# shutter_control.net
KiCad netlist of a schematic drawn in EAGLE
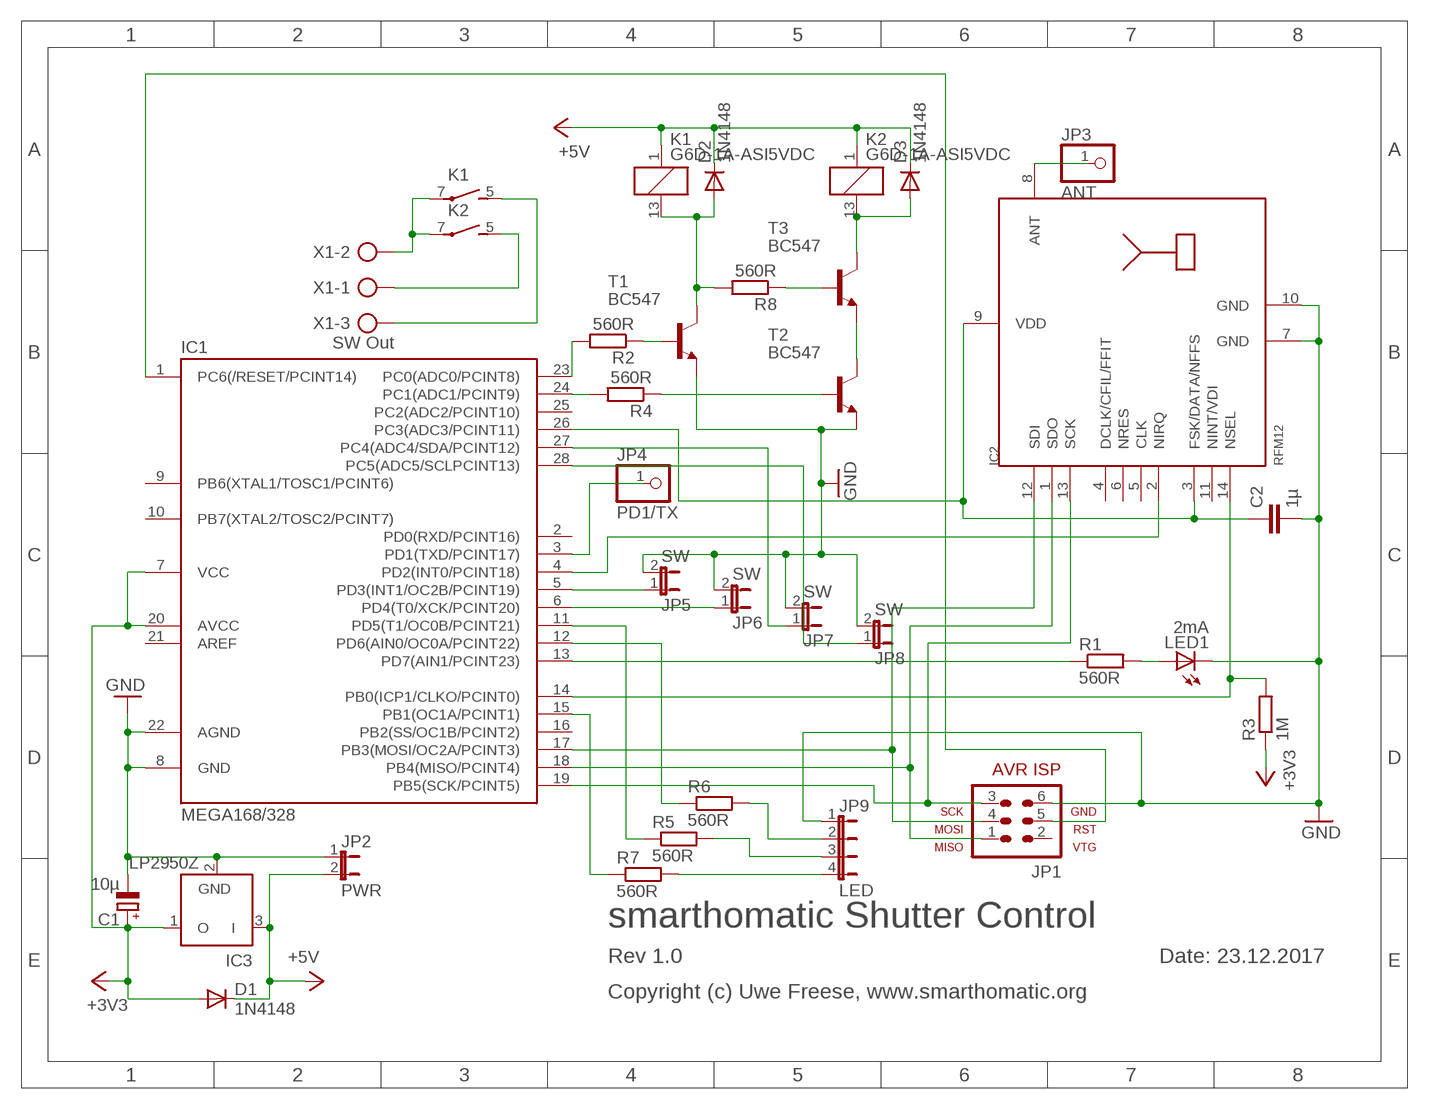
[diagram p0: schematic, sheet 1]

(export (version "E")
  (design (tool "Eeschema 10.0.6"))
  (components
    (comp (ref "C1")
      (value "10µ")
      (footprint "eagle-import:E1,8-4")
      (libsource (lib "eagle-import") (part "CPOL-EUE1.8-4"))
    )
    (comp (ref "C2")
      (value "1µ")
      (footprint "eagle-import:C5B3.5")
      (libsource (lib "eagle-import") (part "C5/3.5"))
    )
    (comp (ref "D1")
      (value "1N4148")
      (footprint "eagle-import:DO35-7")
      (libsource (lib "eagle-import") (part "1N4148DO35-7"))
    )
    (comp (ref "D2")
      (value "1N4148")
      (footprint "eagle-import:DO35-7")
      (libsource (lib "eagle-import") (part "1N4148DO35-7"))
    )
    (comp (ref "D3")
      (value "1N4148")
      (footprint "eagle-import:DO35-7")
      (libsource (lib "eagle-import") (part "1N4148DO35-7"))
    )
    (comp (ref "IC1")
      (value "MEGA168/328")
      (footprint "eagle-import:DIL28-3")
      (libsource (lib "eagle-import") (part "MEGA48/88/168-PU"))
    )
    (comp (ref "IC2")
      (value "RFM12")
      (footprint "eagle-import:RFM")
      (libsource (lib "eagle-import") (part "RFM12"))
    )
    (comp (ref "IC3")
      (value "LP2950Z")
      (footprint "eagle-import:TO92")
      (libsource (lib "eagle-import") (part "LP2950Z"))
    )
    (comp (ref "JP1")
      (value "AVR-ISP-6")
      (footprint "eagle-import:AVR-ISP-6")
      (libsource (lib "eagle-import") (part "AVR-ISP-6"))
    )
    (comp (ref "JP2")
      (value "PWR")
      (footprint "eagle-import:JP1")
      (libsource (lib "eagle-import") (part "JP1E"))
    )
    (comp (ref "JP3")
      (value "ANT")
      (footprint "eagle-import:1X01")
      (libsource (lib "eagle-import") (part "PINHD-1X1"))
    )
    (comp (ref "JP4")
      (value "PD1/TX")
      (footprint "eagle-import:1X01")
      (libsource (lib "eagle-import") (part "PINHD-1X1"))
    )
    (comp (ref "JP5")
      (value "SW")
      (footprint "eagle-import:JP1")
      (libsource (lib "eagle-import") (part "JP1E"))
    )
    (comp (ref "JP6")
      (value "SW")
      (footprint "eagle-import:JP1")
      (libsource (lib "eagle-import") (part "JP1E"))
    )
    (comp (ref "JP7")
      (value "SW")
      (footprint "eagle-import:JP1")
      (libsource (lib "eagle-import") (part "JP1E"))
    )
    (comp (ref "JP8")
      (value "SW")
      (footprint "eagle-import:JP1")
      (libsource (lib "eagle-import") (part "JP1E"))
    )
    (comp (ref "JP9")
      (value "LED")
      (footprint "eagle-import:JP4")
      (libsource (lib "eagle-import") (part "JP4E"))
    )
    (comp (ref "K1")
      (value "G6D-1A-ASI5VDC")
      (footprint "eagle-import:G6D")
      (libsource (lib "eagle-import") (part "G6D?-1A-ASI5VDC"))
    )
    (comp (ref "K2")
      (value "G6D-1A-ASI5VDC")
      (footprint "eagle-import:G6D")
      (libsource (lib "eagle-import") (part "G6D?-1A-ASI5VDC"))
    )
    (comp (ref "LED1")
      (value "2mA")
      (footprint "eagle-import:LED3MM")
      (libsource (lib "eagle-import") (part "LED3MM"))
    )
    (comp (ref "R1")
      (value "560R")
      (footprint "eagle-import:0207_7")
      (libsource (lib "eagle-import") (part "R-EU_0207/7"))
    )
    (comp (ref "R2")
      (value "560R")
      (footprint "eagle-import:0207_7")
      (libsource (lib "eagle-import") (part "R-EU_0207/7"))
    )
    (comp (ref "R3")
      (value "1M")
      (footprint "eagle-import:0207_7")
      (libsource (lib "eagle-import") (part "R-EU_0207/7"))
    )
    (comp (ref "R4")
      (value "560R")
      (footprint "eagle-import:0207_7")
      (libsource (lib "eagle-import") (part "R-EU_0207/7"))
    )
    (comp (ref "R5")
      (value "560R")
      (footprint "eagle-import:0207_7")
      (libsource (lib "eagle-import") (part "R-EU_0207/7"))
    )
    (comp (ref "R6")
      (value "560R")
      (footprint "eagle-import:0207_7")
      (libsource (lib "eagle-import") (part "R-EU_0207/7"))
    )
    (comp (ref "R7")
      (value "560R")
      (footprint "eagle-import:0207_7")
      (libsource (lib "eagle-import") (part "R-EU_0207/7"))
    )
    (comp (ref "R8")
      (value "560R")
      (footprint "eagle-import:0207_7")
      (libsource (lib "eagle-import") (part "R-EU_0207/7"))
    )
    (comp (ref "T1")
      (value "BC547")
      (footprint "eagle-import:TO92")
      (libsource (lib "eagle-import") (part "BC547"))
    )
    (comp (ref "T2")
      (value "BC547")
      (footprint "eagle-import:TO92")
      (libsource (lib "eagle-import") (part "BC547"))
    )
    (comp (ref "T3")
      (value "BC547")
      (footprint "eagle-import:TO92")
      (libsource (lib "eagle-import") (part "BC547"))
    )
    (comp (ref "X1")
      (value "SW Out")
      (footprint "eagle-import:AK500_3")
      (libsource (lib "eagle-import") (part "AK500/3"))
    )
  )
  (nets
    (net (code "1") (name "+3V3") (class "Default")
      (node (ref "C1") (pin "+") (pinfunction "+_+") (pintype "passive"))
      (node (ref "D1") (pin "A") (pinfunction "A_A") (pintype "passive"))
      (node (ref "IC1") (pin "20") (pinfunction "AVCC_20") (pintype "passive"))
      (node (ref "IC1") (pin "7") (pinfunction "VCC_7") (pintype "power_in"))
      (node (ref "IC3") (pin "1") (pinfunction "O_1") (pintype "input"))
      (node (ref "R3") (pin "1") (pinfunction "1_1") (pintype "passive"))
    )
    (net (code "2") (name "+5V") (class "Default")
      (node (ref "D1") (pin "C") (pinfunction "C_C") (pintype "passive"))
      (node (ref "D2") (pin "C") (pinfunction "C_C") (pintype "passive"))
      (node (ref "D3") (pin "C") (pinfunction "C_C") (pintype "passive"))
      (node (ref "IC3") (pin "3") (pinfunction "I_3") (pintype "input"))
      (node (ref "JP2") (pin "2") (pinfunction "2_2") (pintype "passive"))
      (node (ref "K1") (pin "1") (pinfunction "1_1") (pintype "passive"))
      (node (ref "K2") (pin "1") (pinfunction "1_1") (pintype "passive"))
    )
    (net (code "3") (name "GND") (class "Default")
      (node (ref "C1") (pin "-") (pinfunction "-_-") (pintype "passive"))
      (node (ref "C2") (pin "2") (pinfunction "2_2") (pintype "passive"))
      (node (ref "IC1") (pin "22") (pinfunction "AGND_22") (pintype "power_in"))
      (node (ref "IC1") (pin "8") (pinfunction "GND_8") (pintype "power_in"))
      (node (ref "IC2") (pin "10") (pinfunction "GND_10") (pintype "power_in"))
      (node (ref "IC2") (pin "7") (pinfunction "GND_7") (pintype "power_in"))
      (node (ref "IC3") (pin "2") (pinfunction "GND_2") (pintype "power_in"))
      (node (ref "JP1") (pin "6") (pinfunction "6_6") (pintype "passive"))
      (node (ref "JP2") (pin "1") (pinfunction "1_1") (pintype "passive"))
      (node (ref "JP5") (pin "2") (pinfunction "2_2") (pintype "passive"))
      (node (ref "JP6") (pin "2") (pinfunction "2_2") (pintype "passive"))
      (node (ref "JP7") (pin "2") (pinfunction "2_2") (pintype "passive"))
      (node (ref "JP8") (pin "2") (pinfunction "2_2") (pintype "passive"))
      (node (ref "JP9") (pin "1") (pinfunction "1_1") (pintype "passive"))
      (node (ref "LED1") (pin "K") (pinfunction "C_K") (pintype "passive"))
      (node (ref "T1") (pin "1") (pinfunction "E_1") (pintype "passive"))
      (node (ref "T2") (pin "1") (pinfunction "E_1") (pintype "passive"))
    )
    (net (code "4") (name "Net-(IC1-PB0(ICP1{slash}CLKO{slash}PCINT0))") (class "Default")
      (node (ref "IC1") (pin "14") (pinfunction "PB0(ICP1/CLKO/PCINT0)_14") (pintype "bidirectional"))
      (node (ref "IC2") (pin "14") (pinfunction "NSEL_14") (pintype "bidirectional"))
      (node (ref "R3") (pin "2") (pinfunction "2_2") (pintype "passive"))
    )
    (net (code "5") (name "Net-(IC1-PB1(OC1A{slash}PCINT1))") (class "Default")
      (node (ref "IC1") (pin "15") (pinfunction "PB1(OC1A/PCINT1)_15") (pintype "bidirectional"))
      (node (ref "R7") (pin "1") (pinfunction "1_1") (pintype "passive"))
    )
    (net (code "6") (name "Net-(IC1-PB3(MOSI{slash}OC2A{slash}PCINT3))") (class "Default")
      (node (ref "IC1") (pin "17") (pinfunction "PB3(MOSI/OC2A/PCINT3)_17") (pintype "bidirectional"))
      (node (ref "IC2") (pin "12") (pinfunction "SDI_12") (pintype "bidirectional"))
      (node (ref "JP1") (pin "4") (pinfunction "4_4") (pintype "passive"))
    )
    (net (code "7") (name "Net-(IC1-PB4(MISO{slash}PCINT4))") (class "Default")
      (node (ref "IC1") (pin "18") (pinfunction "PB4(MISO/PCINT4)_18") (pintype "bidirectional"))
      (node (ref "IC2") (pin "1") (pinfunction "SDO_1") (pintype "bidirectional"))
      (node (ref "JP1") (pin "1") (pinfunction "1_1") (pintype "passive"))
    )
    (net (code "8") (name "Net-(IC1-PB5(SCK{slash}PCINT5))") (class "Default")
      (node (ref "IC1") (pin "19") (pinfunction "PB5(SCK/PCINT5)_19") (pintype "bidirectional"))
      (node (ref "IC2") (pin "13") (pinfunction "SCK_13") (pintype "bidirectional"))
      (node (ref "JP1") (pin "3") (pinfunction "3_3") (pintype "passive"))
    )
    (net (code "9") (name "Net-(IC1-PC0(ADC0{slash}PCINT8))") (class "Default")
      (node (ref "IC1") (pin "23") (pinfunction "PC0(ADC0/PCINT8)_23") (pintype "bidirectional"))
      (node (ref "R2") (pin "2") (pinfunction "2_2") (pintype "passive"))
    )
    (net (code "10") (name "Net-(IC1-PC1(ADC1{slash}PCINT9))") (class "Default")
      (node (ref "IC1") (pin "24") (pinfunction "PC1(ADC1/PCINT9)_24") (pintype "bidirectional"))
      (node (ref "R4") (pin "2") (pinfunction "2_2") (pintype "passive"))
    )
    (net (code "11") (name "Net-(IC1-PC3(ADC3{slash}PCINT11))") (class "Default")
      (node (ref "C2") (pin "1") (pinfunction "1_1") (pintype "passive"))
      (node (ref "IC1") (pin "26") (pinfunction "PC3(ADC3/PCINT11)_26") (pintype "bidirectional"))
      (node (ref "IC2") (pin "3") (pinfunction "FSK/DATA/NFFS_3") (pintype "bidirectional"))
      (node (ref "IC2") (pin "9") (pinfunction "VDD_9") (pintype "power_in"))
    )
    (net (code "12") (name "Net-(IC1-PC4(ADC4{slash}SDA{slash}PCINT12))") (class "Default")
      (node (ref "IC1") (pin "27") (pinfunction "PC4(ADC4/SDA/PCINT12)_27") (pintype "bidirectional"))
      (node (ref "JP7") (pin "1") (pinfunction "1_1") (pintype "passive"))
    )
    (net (code "13") (name "Net-(IC1-PC5(ADC5{slash}SCLPCINT13))") (class "Default")
      (node (ref "IC1") (pin "28") (pinfunction "PC5(ADC5/SCLPCINT13)_28") (pintype "bidirectional"))
      (node (ref "JP8") (pin "1") (pinfunction "1_1") (pintype "passive"))
    )
    (net (code "14") (name "Net-(IC1-PC6({slash}RESET{slash}PCINT14))") (class "Default")
      (node (ref "IC1") (pin "1") (pinfunction "PC6(/RESET/PCINT14)_1") (pintype "bidirectional"))
      (node (ref "JP1") (pin "5") (pinfunction "5_5") (pintype "passive"))
    )
    (net (code "15") (name "Net-(IC1-PD1(TXD{slash}PCINT17))") (class "Default")
      (node (ref "IC1") (pin "3") (pinfunction "PD1(TXD/PCINT17)_3") (pintype "bidirectional"))
      (node (ref "JP4") (pin "1") (pinfunction "1_1") (pintype "passive"))
    )
    (net (code "16") (name "Net-(IC1-PD2(INT0{slash}PCINT18))") (class "Default")
      (node (ref "IC1") (pin "4") (pinfunction "PD2(INT0/PCINT18)_4") (pintype "bidirectional"))
      (node (ref "IC2") (pin "2") (pinfunction "NIRQ_2") (pintype "bidirectional"))
    )
    (net (code "17") (name "Net-(IC1-PD3(INT1{slash}OC2B{slash}PCINT19))") (class "Default")
      (node (ref "IC1") (pin "5") (pinfunction "PD3(INT1/OC2B/PCINT19)_5") (pintype "bidirectional"))
      (node (ref "JP5") (pin "1") (pinfunction "1_1") (pintype "passive"))
    )
    (net (code "18") (name "Net-(IC1-PD4(T0{slash}XCK{slash}PCINT20))") (class "Default")
      (node (ref "IC1") (pin "6") (pinfunction "PD4(T0/XCK/PCINT20)_6") (pintype "bidirectional"))
      (node (ref "JP6") (pin "1") (pinfunction "1_1") (pintype "passive"))
    )
    (net (code "19") (name "Net-(IC1-PD5(T1{slash}OC0B{slash}PCINT21))") (class "Default")
      (node (ref "IC1") (pin "11") (pinfunction "PD5(T1/OC0B/PCINT21)_11") (pintype "bidirectional"))
      (node (ref "R5") (pin "1") (pinfunction "1_1") (pintype "passive"))
    )
    (net (code "20") (name "Net-(IC1-PD6(AIN0{slash}OC0A{slash}PCINT22))") (class "Default")
      (node (ref "IC1") (pin "12") (pinfunction "PD6(AIN0/OC0A/PCINT22)_12") (pintype "bidirectional"))
      (node (ref "R6") (pin "1") (pinfunction "1_1") (pintype "passive"))
    )
    (net (code "21") (name "Net-(IC1-PD7(AIN1{slash}PCINT23))") (class "Default")
      (node (ref "IC1") (pin "13") (pinfunction "PD7(AIN1/PCINT23)_13") (pintype "bidirectional"))
      (node (ref "R1") (pin "1") (pinfunction "1_1") (pintype "passive"))
    )
    (net (code "22") (name "Net-(IC2-ANT)") (class "Default")
      (node (ref "IC2") (pin "8") (pinfunction "ANT_8") (pintype "output"))
      (node (ref "JP3") (pin "1") (pinfunction "1_1") (pintype "passive"))
    )
    (net (code "23") (name "Net-(JP9-Pad2)") (class "Default")
      (node (ref "JP9") (pin "2") (pinfunction "2_2") (pintype "passive"))
      (node (ref "R6") (pin "2") (pinfunction "2_2") (pintype "passive"))
    )
    (net (code "24") (name "Net-(JP9-Pad3)") (class "Default")
      (node (ref "JP9") (pin "3") (pinfunction "3_3") (pintype "passive"))
      (node (ref "R5") (pin "2") (pinfunction "2_2") (pintype "passive"))
    )
    (net (code "25") (name "Net-(JP9-Pad4)") (class "Default")
      (node (ref "JP9") (pin "4") (pinfunction "4_4") (pintype "passive"))
      (node (ref "R7") (pin "2") (pinfunction "2_2") (pintype "passive"))
    )
    (net (code "26") (name "Net-(K1A-2)") (class "Default")
      (node (ref "D2") (pin "A") (pinfunction "A_A") (pintype "passive"))
      (node (ref "K1") (pin "13") (pinfunction "2_13") (pintype "passive"))
      (node (ref "R8") (pin "2") (pinfunction "2_2") (pintype "passive"))
      (node (ref "T1") (pin "3") (pinfunction "C_3") (pintype "passive"))
    )
    (net (code "27") (name "Net-(K1B-P)") (class "Default")
      (node (ref "K1") (pin "7") (pinfunction "P_7") (pintype "passive"))
      (node (ref "K2") (pin "7") (pinfunction "P_7") (pintype "passive"))
      (node (ref "X1") (pin "2") (pinfunction "KL_2") (pintype "passive"))
    )
    (net (code "28") (name "Net-(K1B-S)") (class "Default")
      (node (ref "K1") (pin "5") (pinfunction "S_5") (pintype "passive"))
      (node (ref "X1") (pin "3") (pinfunction "KL_3") (pintype "passive"))
    )
    (net (code "29") (name "Net-(K2A-2)") (class "Default")
      (node (ref "D3") (pin "A") (pinfunction "A_A") (pintype "passive"))
      (node (ref "K2") (pin "13") (pinfunction "2_13") (pintype "passive"))
      (node (ref "T3") (pin "3") (pinfunction "C_3") (pintype "passive"))
    )
    (net (code "30") (name "Net-(K2B-S)") (class "Default")
      (node (ref "K2") (pin "5") (pinfunction "S_5") (pintype "passive"))
      (node (ref "X1") (pin "1") (pinfunction "KL_1") (pintype "passive"))
    )
    (net (code "31") (name "Net-(LED1-PadA)") (class "Default")
      (node (ref "LED1") (pin "A") (pinfunction "A_A") (pintype "passive"))
      (node (ref "R1") (pin "2") (pinfunction "2_2") (pintype "passive"))
    )
    (net (code "32") (name "Net-(T1-B)") (class "Default")
      (node (ref "R2") (pin "1") (pinfunction "1_1") (pintype "passive"))
      (node (ref "T1") (pin "2") (pinfunction "B_2") (pintype "passive"))
    )
    (net (code "33") (name "Net-(T2-B)") (class "Default")
      (node (ref "R4") (pin "1") (pinfunction "1_1") (pintype "passive"))
      (node (ref "T2") (pin "2") (pinfunction "B_2") (pintype "passive"))
    )
    (net (code "34") (name "Net-(T2-C)") (class "Default")
      (node (ref "T2") (pin "3") (pinfunction "C_3") (pintype "passive"))
      (node (ref "T3") (pin "1") (pinfunction "E_1") (pintype "passive"))
    )
    (net (code "35") (name "Net-(T3-B)") (class "Default")
      (node (ref "R8") (pin "1") (pinfunction "1_1") (pintype "passive"))
      (node (ref "T3") (pin "2") (pinfunction "B_2") (pintype "passive"))
    )
    (net (code "36") (name "unconnected-(IC1-AREF-Pad21)") (class "Default")
      (node (ref "IC1") (pin "21") (pinfunction "AREF_21") (pintype "passive"))
    )
    (net (code "37") (name "unconnected-(IC1-PB2(SS{slash}OC1B{slash}PCINT2)-Pad16)") (class "Default")
      (node (ref "IC1") (pin "16") (pinfunction "PB2(SS/OC1B/PCINT2)_16") (pintype "bidirectional"))
    )
    (net (code "38") (name "unconnected-(IC1-PB6(XTAL1{slash}TOSC1{slash}PCINT6)-Pad9)") (class "Default")
      (node (ref "IC1") (pin "9") (pinfunction "PB6(XTAL1/TOSC1/PCINT6)_9") (pintype "bidirectional"))
    )
    (net (code "39") (name "unconnected-(IC1-PB7(XTAL2{slash}TOSC2{slash}PCINT7)-Pad10)") (class "Default")
      (node (ref "IC1") (pin "10") (pinfunction "PB7(XTAL2/TOSC2/PCINT7)_10") (pintype "bidirectional"))
    )
    (net (code "40") (name "unconnected-(IC1-PC2(ADC2{slash}PCINT10)-Pad25)") (class "Default")
      (node (ref "IC1") (pin "25") (pinfunction "PC2(ADC2/PCINT10)_25") (pintype "bidirectional"))
    )
    (net (code "41") (name "unconnected-(IC1-PD0(RXD{slash}PCINT16)-Pad2)") (class "Default")
      (node (ref "IC1") (pin "2") (pinfunction "PD0(RXD/PCINT16)_2") (pintype "bidirectional"))
    )
    (net (code "42") (name "unconnected-(IC2-CLK-Pad5)") (class "Default")
      (node (ref "IC2") (pin "5") (pinfunction "CLK_5") (pintype "bidirectional"))
    )
    (net (code "43") (name "unconnected-(IC2-DCLK{slash}CFIL{slash}FFIT-Pad4)") (class "Default")
      (node (ref "IC2") (pin "4") (pinfunction "DCLK/CFIL/FFIT_4") (pintype "bidirectional"))
    )
    (net (code "44") (name "unconnected-(IC2-NINT{slash}VDI-Pad11)") (class "Default")
      (node (ref "IC2") (pin "11") (pinfunction "NINT/VDI_11") (pintype "bidirectional"))
    )
    (net (code "45") (name "unconnected-(IC2-NRES-Pad6)") (class "Default")
      (node (ref "IC2") (pin "6") (pinfunction "NRES_6") (pintype "bidirectional"))
    )
    (net (code "46") (name "unconnected-(JP1-Pad2)") (class "Default")
      (node (ref "JP1") (pin "2") (pinfunction "2_2") (pintype "passive"))
    )
  )
)
